# SDMAC.net
KiCad netlist of a schematic drawn in EAGLE
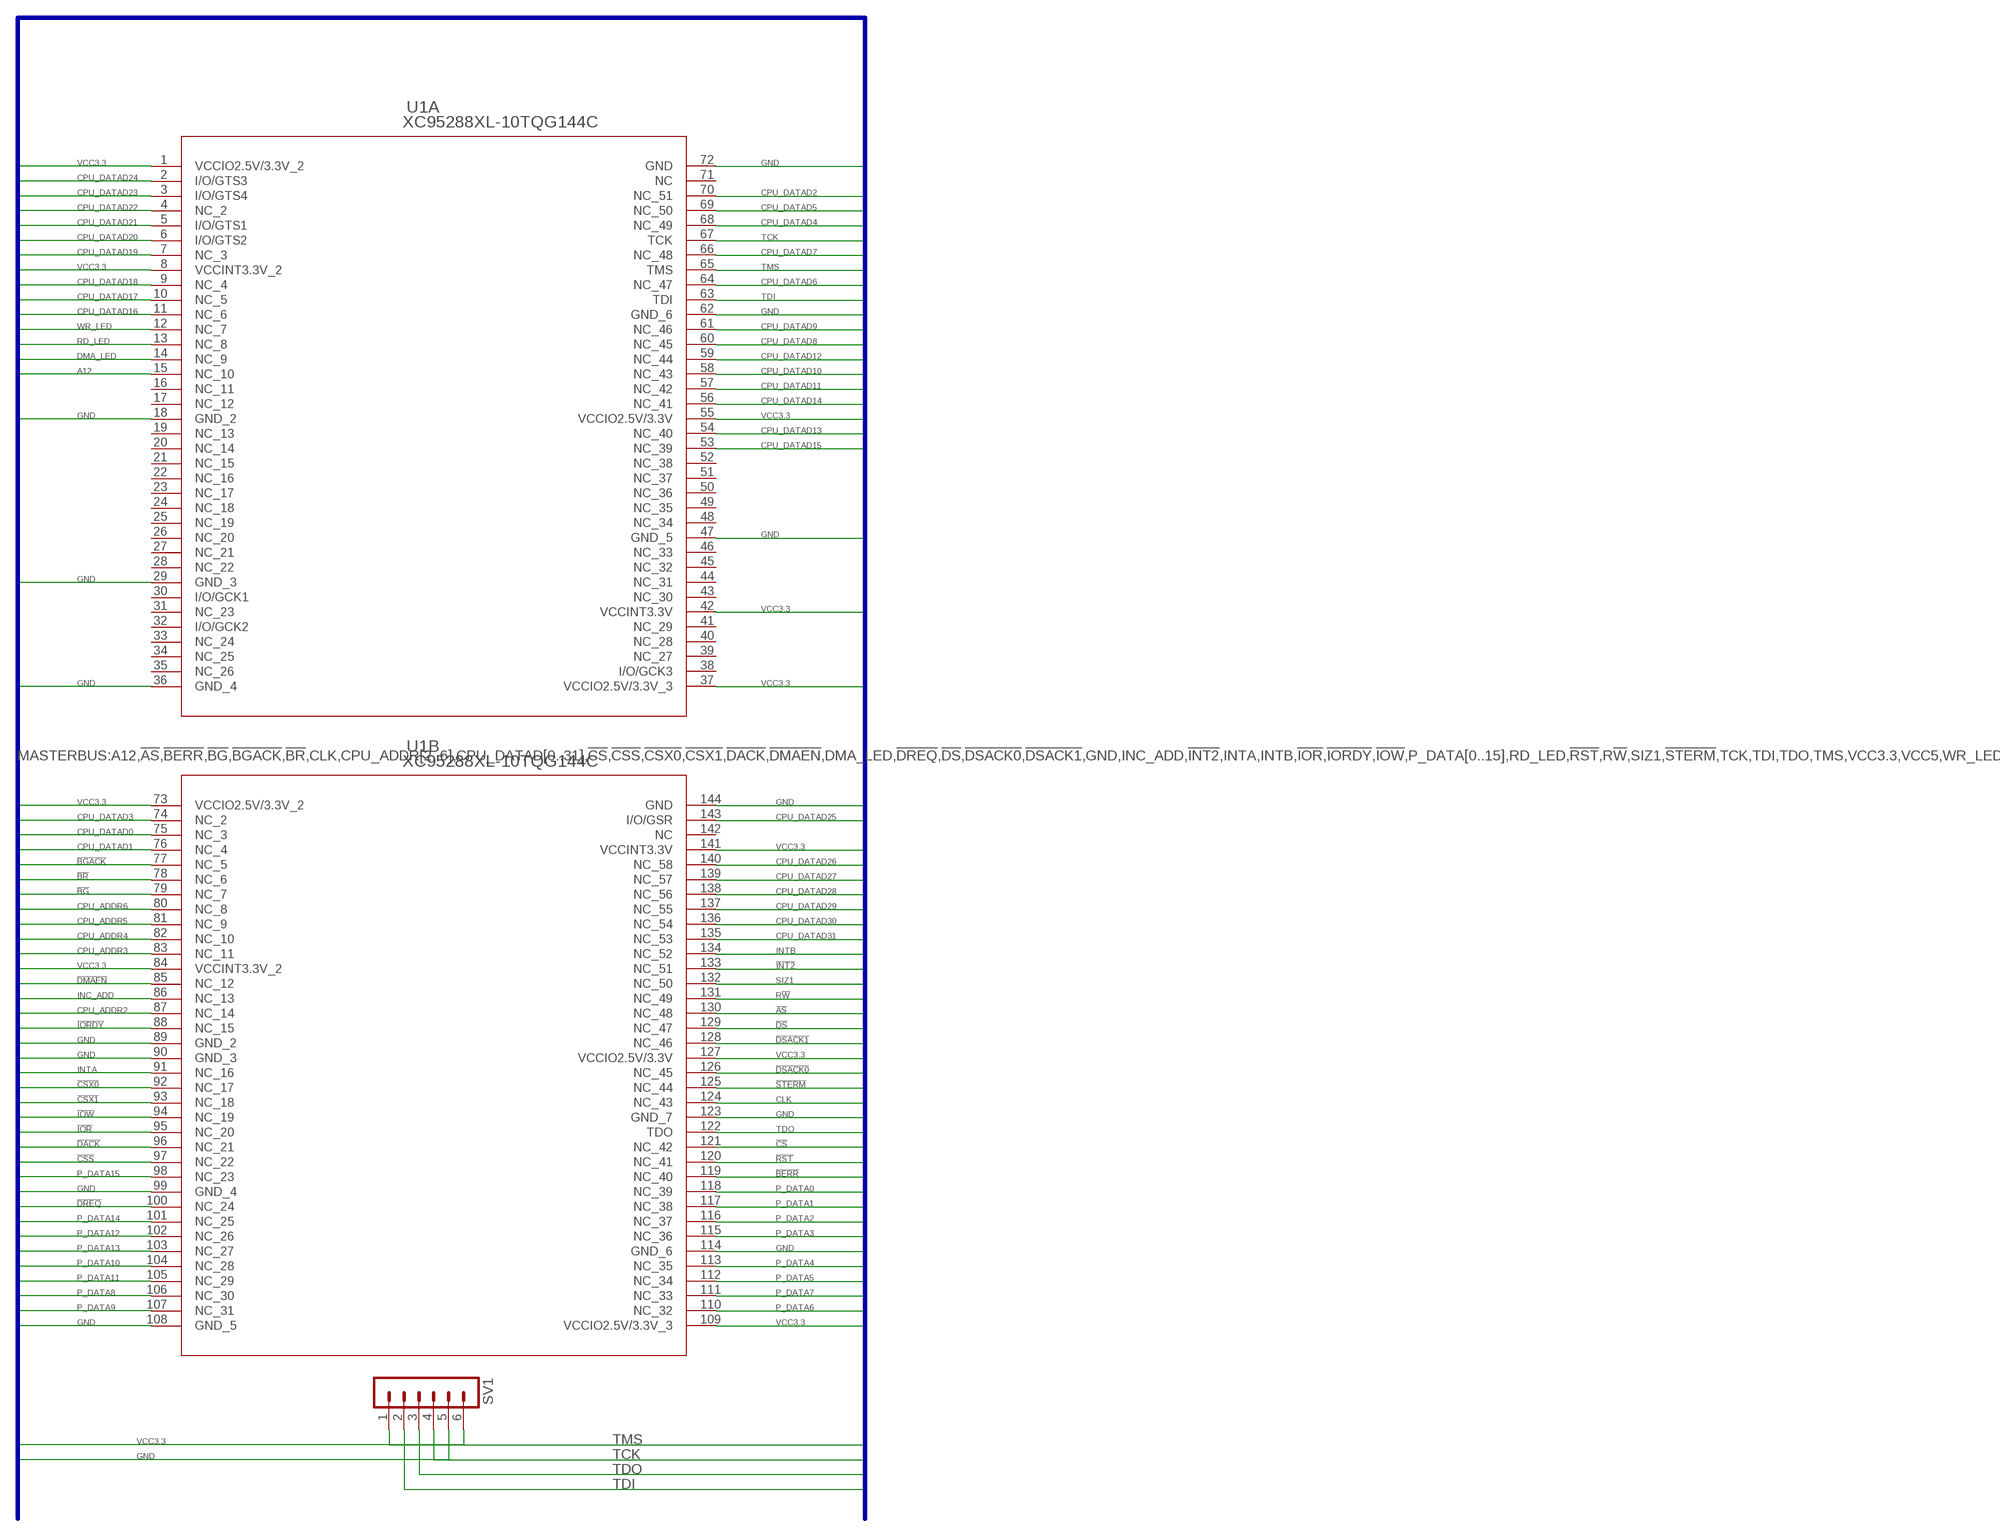
[diagram p0: schematic, sheet 1]
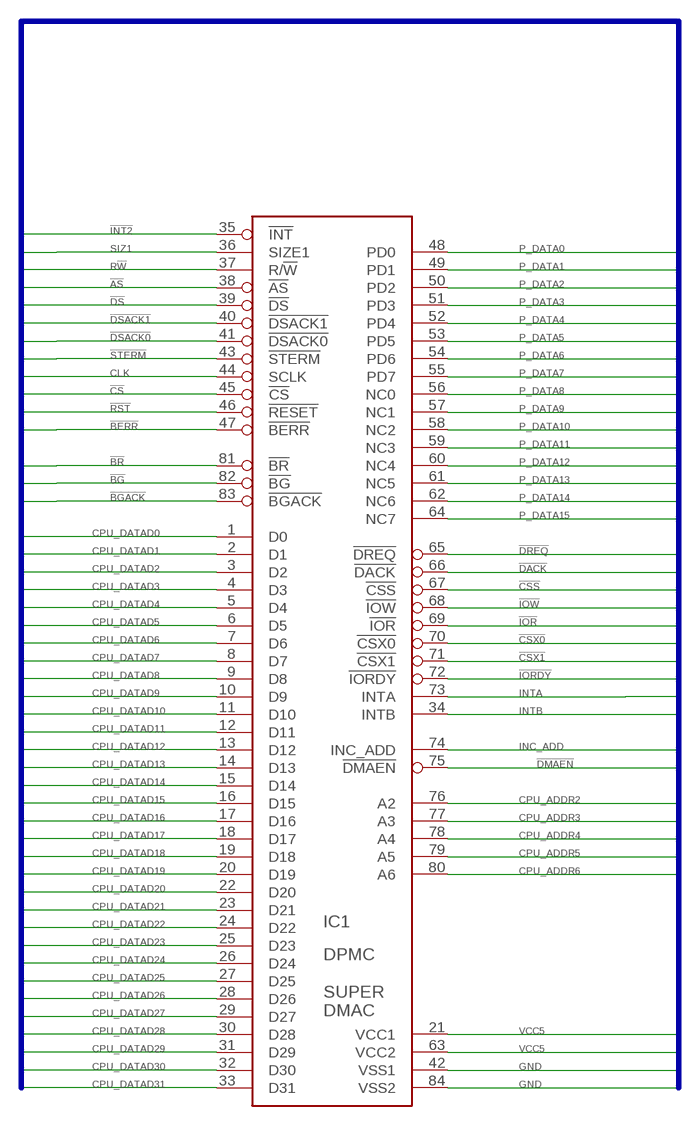
[diagram p1: schematic, sheet 2]
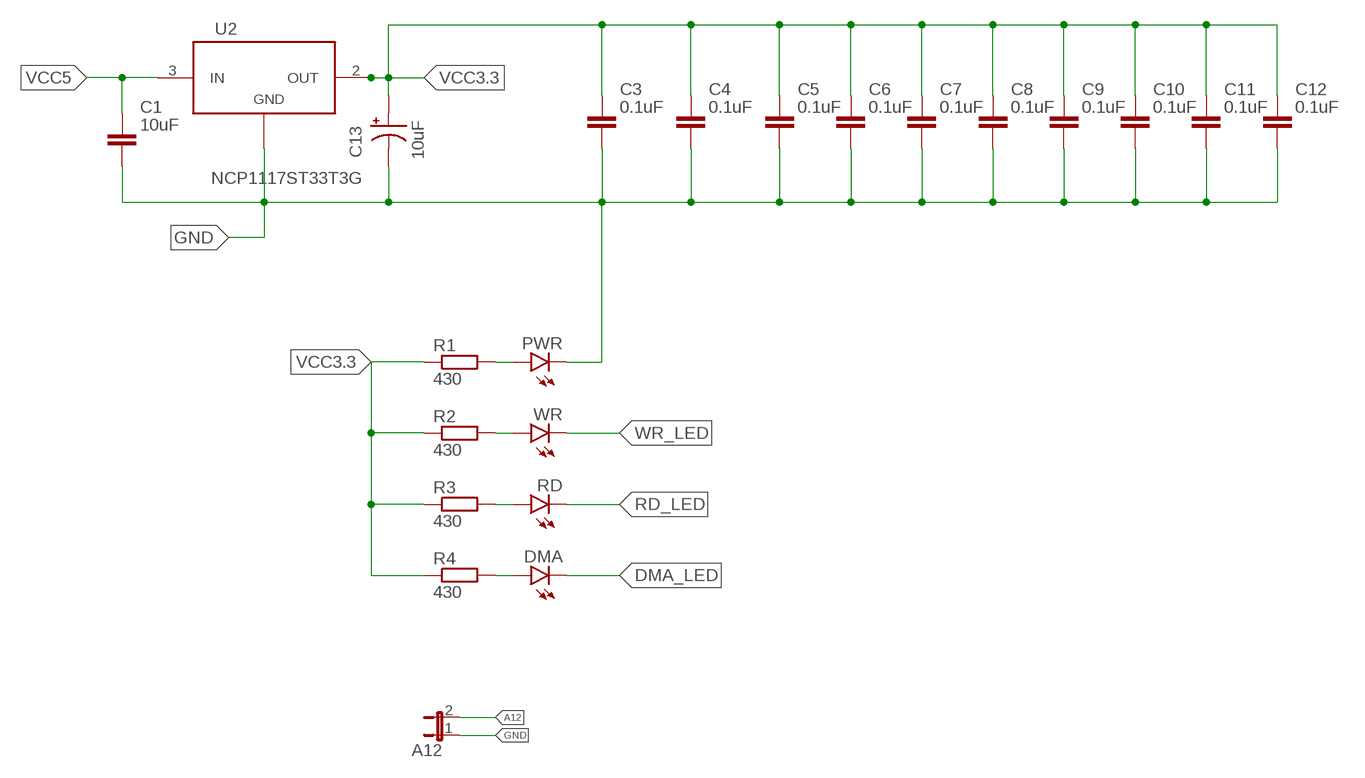
[diagram p2: schematic, sheet 3]

(export (version "E")
  (design (tool "Eeschema 10.0.6"))
  (components
    (comp (ref "IC1")
      (value "SUPER_DMAC_THT")
      (footprint "eagle-import:PLCC84_T")
      (libsource (lib "eagle-import") (part "SUPER_DMAC_THT"))
    )
    (comp (ref "A12")
      (value "JP1E")
      (footprint "eagle-import:JP1")
      (libsource (lib "eagle-import") (part "JP1E"))
    )
    (comp (ref "C1")
      (value "10uF")
      (footprint "eagle-import:CAPC2012X110")
      (libsource (lib "eagle-import") (part "CCHIP-0805(2012-METRIC)_"))
    )
    (comp (ref "C3")
      (value "0.1uF")
      (footprint "eagle-import:CAPC2012X110")
      (libsource (lib "eagle-import") (part "CCHIP-0805(2012-METRIC)_"))
    )
    (comp (ref "C4")
      (value "0.1uF")
      (footprint "eagle-import:CAPC2012X110")
      (libsource (lib "eagle-import") (part "CCHIP-0805(2012-METRIC)_"))
    )
    (comp (ref "C5")
      (value "0.1uF")
      (footprint "eagle-import:CAPC2012X110")
      (libsource (lib "eagle-import") (part "CCHIP-0805(2012-METRIC)_"))
    )
    (comp (ref "C6")
      (value "0.1uF")
      (footprint "eagle-import:CAPC2012X110")
      (libsource (lib "eagle-import") (part "CCHIP-0805(2012-METRIC)_"))
    )
    (comp (ref "C7")
      (value "0.1uF")
      (footprint "eagle-import:CAPC2012X110")
      (libsource (lib "eagle-import") (part "CCHIP-0805(2012-METRIC)_"))
    )
    (comp (ref "C8")
      (value "0.1uF")
      (footprint "eagle-import:CAPC2012X110")
      (libsource (lib "eagle-import") (part "CCHIP-0805(2012-METRIC)_"))
    )
    (comp (ref "C9")
      (value "0.1uF")
      (footprint "eagle-import:CAPC2012X110")
      (libsource (lib "eagle-import") (part "CCHIP-0805(2012-METRIC)_"))
    )
    (comp (ref "C10")
      (value "0.1uF")
      (footprint "eagle-import:CAPC2012X110")
      (libsource (lib "eagle-import") (part "CCHIP-0805(2012-METRIC)_"))
    )
    (comp (ref "C11")
      (value "0.1uF")
      (footprint "eagle-import:CAPC2012X110")
      (libsource (lib "eagle-import") (part "CCHIP-0805(2012-METRIC)_"))
    )
    (comp (ref "C12")
      (value "0.1uF")
      (footprint "eagle-import:CAPC2012X110")
      (libsource (lib "eagle-import") (part "CCHIP-0805(2012-METRIC)_"))
    )
    (comp (ref "C13")
      (value "10uF")
      (footprint "eagle-import:A")
      (fields
        (field (name "MANUFACTURER") "Kemet")
        (field (name "PART_NUMBER") "T491A106K010AT")
        (field (name "TOLERANCE") "±10%")
      )
      (libsource (lib "eagle-import") (part "T491?A106K010AT"))
    )
    (comp (ref "DMA")
      (value "LEDSML0805")
      (footprint "eagle-import:SML0805")
      (libsource (lib "eagle-import") (part "LEDSML0805"))
    )
    (comp (ref "PWR")
      (value "LEDSML0805")
      (footprint "eagle-import:SML0805")
      (libsource (lib "eagle-import") (part "LEDSML0805"))
    )
    (comp (ref "R1")
      (value "430")
      (footprint "eagle-import:R0805")
      (libsource (lib "eagle-import") (part "R-EU_R0805"))
    )
    (comp (ref "R2")
      (value "430")
      (footprint "eagle-import:R0805")
      (libsource (lib "eagle-import") (part "R-EU_R0805"))
    )
    (comp (ref "R3")
      (value "430")
      (footprint "eagle-import:R0805")
      (libsource (lib "eagle-import") (part "R-EU_R0805"))
    )
    (comp (ref "R4")
      (value "430")
      (footprint "eagle-import:R0805")
      (libsource (lib "eagle-import") (part "R-EU_R0805"))
    )
    (comp (ref "RD")
      (value "LEDSML0805")
      (footprint "eagle-import:SML0805")
      (libsource (lib "eagle-import") (part "LEDSML0805"))
    )
    (comp (ref "U2")
      (value "NCP1117ST33T3G")
      (footprint "eagle-import:SOT-223")
      (fields
        (field (name "DIGIKEY_PART_NUMBER") "NCP1117ST33T3GOSTR-ND")
        (field (name "MANUFACTURER") "ON Semiconductor")
        (field (name "CREATED_BY") "PCBLayout.com")
      )
      (libsource (lib "eagle-import") (part "NCP1117ST33T3G"))
    )
    (comp (ref "WR")
      (value "LEDSML0805")
      (footprint "eagle-import:SML0805")
      (libsource (lib "eagle-import") (part "LEDSML0805"))
    )
    (comp (ref "SV1")
      (value "MA06-1")
      (footprint "eagle-import:MA06-1")
      (fields (field (name "SPICEPREFIX") "X"))
      (libsource (lib "eagle-import") (part "MA06-1"))
    )
    (comp (ref "U1")
      (value "XC95288XL-10TQG144C")
      (footprint "eagle-import:144-TQFP_XIL")
      (fields (field (name "COPYRIGHT") "Copyright (C) 2022 Ultra Librarian. All rights reserved."))
      (libsource (lib "eagle-import") (part "XC95288XL-10TQG144C"))
    )
  )
  (nets
    (net (code "4") (name "A12") (class "Default")
      (node (ref "A12") (pin "2") (pinfunction "2_2") (pintype "passive"))
      (node (ref "U1") (pin "15") (pinfunction "NC_10_15") (pintype "passive"))
    )
    (net (code "5") (name "CLK") (class "Default")
      (node (ref "IC1") (pin "44") (pinfunction "SCLK_44") (pintype "input"))
      (node (ref "U1") (pin "124") (pinfunction "NC_43_124") (pintype "passive"))
    )
    (net (code "6") (name "CPU_ADDR2") (class "Default")
      (node (ref "IC1") (pin "76") (pinfunction "A2_76") (pintype "input"))
      (node (ref "U1") (pin "87") (pinfunction "NC_14_87") (pintype "passive"))
    )
    (net (code "7") (name "CPU_ADDR3") (class "Default")
      (node (ref "IC1") (pin "77") (pinfunction "A3_77") (pintype "input"))
      (node (ref "U1") (pin "83") (pinfunction "NC_11_83") (pintype "passive"))
    )
    (net (code "8") (name "CPU_ADDR4") (class "Default")
      (node (ref "IC1") (pin "78") (pinfunction "A4_78") (pintype "input"))
      (node (ref "U1") (pin "82") (pinfunction "NC_10_82") (pintype "passive"))
    )
    (net (code "9") (name "CPU_ADDR5") (class "Default")
      (node (ref "IC1") (pin "79") (pinfunction "A5_79") (pintype "input"))
      (node (ref "U1") (pin "81") (pinfunction "NC_9_81") (pintype "passive"))
    )
    (net (code "10") (name "CPU_ADDR6") (class "Default")
      (node (ref "IC1") (pin "80") (pinfunction "A6_80") (pintype "input"))
      (node (ref "U1") (pin "80") (pinfunction "NC_8_80") (pintype "passive"))
    )
    (net (code "11") (name "CPU_DATAD0") (class "Default")
      (node (ref "IC1") (pin "1") (pinfunction "D0_1") (pintype "bidirectional"))
      (node (ref "U1") (pin "75") (pinfunction "NC_3_75") (pintype "passive"))
    )
    (net (code "12") (name "CPU_DATAD1") (class "Default")
      (node (ref "IC1") (pin "2") (pinfunction "D1_2") (pintype "bidirectional"))
      (node (ref "U1") (pin "76") (pinfunction "NC_4_76") (pintype "passive"))
    )
    (net (code "13") (name "CPU_DATAD2") (class "Default")
      (node (ref "IC1") (pin "3") (pinfunction "D2_3") (pintype "bidirectional"))
      (node (ref "U1") (pin "70") (pinfunction "NC_51_70") (pintype "passive"))
    )
    (net (code "14") (name "CPU_DATAD3") (class "Default")
      (node (ref "IC1") (pin "4") (pinfunction "D3_4") (pintype "bidirectional"))
      (node (ref "U1") (pin "74") (pinfunction "NC_2_74") (pintype "passive"))
    )
    (net (code "15") (name "CPU_DATAD4") (class "Default")
      (node (ref "IC1") (pin "5") (pinfunction "D4_5") (pintype "bidirectional"))
      (node (ref "U1") (pin "68") (pinfunction "NC_49_68") (pintype "passive"))
    )
    (net (code "16") (name "CPU_DATAD5") (class "Default")
      (node (ref "IC1") (pin "6") (pinfunction "D5_6") (pintype "bidirectional"))
      (node (ref "U1") (pin "69") (pinfunction "NC_50_69") (pintype "passive"))
    )
    (net (code "17") (name "CPU_DATAD6") (class "Default")
      (node (ref "IC1") (pin "7") (pinfunction "D6_7") (pintype "bidirectional"))
      (node (ref "U1") (pin "64") (pinfunction "NC_47_64") (pintype "passive"))
    )
    (net (code "18") (name "CPU_DATAD7") (class "Default")
      (node (ref "IC1") (pin "8") (pinfunction "D7_8") (pintype "bidirectional"))
      (node (ref "U1") (pin "66") (pinfunction "NC_48_66") (pintype "passive"))
    )
    (net (code "19") (name "CPU_DATAD8") (class "Default")
      (node (ref "IC1") (pin "9") (pinfunction "D8_9") (pintype "bidirectional"))
      (node (ref "U1") (pin "60") (pinfunction "NC_45_60") (pintype "passive"))
    )
    (net (code "20") (name "CPU_DATAD9") (class "Default")
      (node (ref "IC1") (pin "10") (pinfunction "D9_10") (pintype "bidirectional"))
      (node (ref "U1") (pin "61") (pinfunction "NC_46_61") (pintype "passive"))
    )
    (net (code "21") (name "CPU_DATAD10") (class "Default")
      (node (ref "IC1") (pin "11") (pinfunction "D10_11") (pintype "bidirectional"))
      (node (ref "U1") (pin "58") (pinfunction "NC_43_58") (pintype "passive"))
    )
    (net (code "22") (name "CPU_DATAD11") (class "Default")
      (node (ref "IC1") (pin "12") (pinfunction "D11_12") (pintype "bidirectional"))
      (node (ref "U1") (pin "57") (pinfunction "NC_42_57") (pintype "passive"))
    )
    (net (code "23") (name "CPU_DATAD12") (class "Default")
      (node (ref "IC1") (pin "13") (pinfunction "D12_13") (pintype "bidirectional"))
      (node (ref "U1") (pin "59") (pinfunction "NC_44_59") (pintype "passive"))
    )
    (net (code "24") (name "CPU_DATAD13") (class "Default")
      (node (ref "IC1") (pin "14") (pinfunction "D13_14") (pintype "bidirectional"))
      (node (ref "U1") (pin "54") (pinfunction "NC_40_54") (pintype "passive"))
    )
    (net (code "25") (name "CPU_DATAD14") (class "Default")
      (node (ref "IC1") (pin "15") (pinfunction "D14_15") (pintype "bidirectional"))
      (node (ref "U1") (pin "56") (pinfunction "NC_41_56") (pintype "passive"))
    )
    (net (code "26") (name "CPU_DATAD15") (class "Default")
      (node (ref "IC1") (pin "16") (pinfunction "D15_16") (pintype "bidirectional"))
      (node (ref "U1") (pin "53") (pinfunction "NC_39_53") (pintype "passive"))
    )
    (net (code "27") (name "CPU_DATAD16") (class "Default")
      (node (ref "IC1") (pin "17") (pinfunction "D16_17") (pintype "bidirectional"))
      (node (ref "U1") (pin "11") (pinfunction "NC_6_11") (pintype "passive"))
    )
    (net (code "28") (name "CPU_DATAD17") (class "Default")
      (node (ref "IC1") (pin "18") (pinfunction "D17_18") (pintype "bidirectional"))
      (node (ref "U1") (pin "10") (pinfunction "NC_5_10") (pintype "passive"))
    )
    (net (code "29") (name "CPU_DATAD18") (class "Default")
      (node (ref "IC1") (pin "19") (pinfunction "D18_19") (pintype "bidirectional"))
      (node (ref "U1") (pin "9") (pinfunction "NC_4_9") (pintype "passive"))
    )
    (net (code "30") (name "CPU_DATAD19") (class "Default")
      (node (ref "IC1") (pin "20") (pinfunction "D19_20") (pintype "bidirectional"))
      (node (ref "U1") (pin "7") (pinfunction "NC_3_7") (pintype "passive"))
    )
    (net (code "31") (name "CPU_DATAD20") (class "Default")
      (node (ref "IC1") (pin "22") (pinfunction "D20_22") (pintype "bidirectional"))
      (node (ref "U1") (pin "6") (pinfunction "I/O/GTS2_6") (pintype "bidirectional"))
    )
    (net (code "32") (name "CPU_DATAD21") (class "Default")
      (node (ref "IC1") (pin "23") (pinfunction "D21_23") (pintype "bidirectional"))
      (node (ref "U1") (pin "5") (pinfunction "I/O/GTS1_5") (pintype "bidirectional"))
    )
    (net (code "33") (name "CPU_DATAD22") (class "Default")
      (node (ref "IC1") (pin "24") (pinfunction "D22_24") (pintype "bidirectional"))
      (node (ref "U1") (pin "4") (pinfunction "NC_2_4") (pintype "passive"))
    )
    (net (code "34") (name "CPU_DATAD23") (class "Default")
      (node (ref "IC1") (pin "25") (pinfunction "D23_25") (pintype "bidirectional"))
      (node (ref "U1") (pin "3") (pinfunction "I/O/GTS4_3") (pintype "bidirectional"))
    )
    (net (code "35") (name "CPU_DATAD24") (class "Default")
      (node (ref "IC1") (pin "26") (pinfunction "D24_26") (pintype "bidirectional"))
      (node (ref "U1") (pin "2") (pinfunction "I/O/GTS3_2") (pintype "bidirectional"))
    )
    (net (code "36") (name "CPU_DATAD25") (class "Default")
      (node (ref "IC1") (pin "27") (pinfunction "D25_27") (pintype "bidirectional"))
      (node (ref "U1") (pin "143") (pinfunction "I/O/GSR_143") (pintype "bidirectional"))
    )
    (net (code "37") (name "CPU_DATAD26") (class "Default")
      (node (ref "IC1") (pin "28") (pinfunction "D26_28") (pintype "bidirectional"))
      (node (ref "U1") (pin "140") (pinfunction "NC_58_140") (pintype "passive"))
    )
    (net (code "38") (name "CPU_DATAD27") (class "Default")
      (node (ref "IC1") (pin "29") (pinfunction "D27_29") (pintype "bidirectional"))
      (node (ref "U1") (pin "139") (pinfunction "NC_57_139") (pintype "passive"))
    )
    (net (code "39") (name "CPU_DATAD28") (class "Default")
      (node (ref "IC1") (pin "30") (pinfunction "D28_30") (pintype "bidirectional"))
      (node (ref "U1") (pin "138") (pinfunction "NC_56_138") (pintype "passive"))
    )
    (net (code "40") (name "CPU_DATAD29") (class "Default")
      (node (ref "IC1") (pin "31") (pinfunction "D29_31") (pintype "bidirectional"))
      (node (ref "U1") (pin "137") (pinfunction "NC_55_137") (pintype "passive"))
    )
    (net (code "41") (name "CPU_DATAD30") (class "Default")
      (node (ref "IC1") (pin "32") (pinfunction "D30_32") (pintype "bidirectional"))
      (node (ref "U1") (pin "136") (pinfunction "NC_54_136") (pintype "passive"))
    )
    (net (code "42") (name "CPU_DATAD31") (class "Default")
      (node (ref "IC1") (pin "33") (pinfunction "D31_33") (pintype "bidirectional"))
      (node (ref "U1") (pin "135") (pinfunction "NC_53_135") (pintype "passive"))
    )
    (net (code "43") (name "DMA_LED") (class "Default")
      (node (ref "DMA") (pin "C") (pinfunction "C_C") (pintype "passive"))
      (node (ref "U1") (pin "14") (pinfunction "NC_9_14") (pintype "passive"))
    )
    (net (code "44") (name "GND") (class "Default")
      (node (ref "A12") (pin "1") (pinfunction "1_1") (pintype "passive"))
      (node (ref "C1") (pin "2") (pinfunction "2_2") (pintype "passive"))
      (node (ref "C10") (pin "2") (pinfunction "2_2") (pintype "passive"))
      (node (ref "C11") (pin "2") (pinfunction "2_2") (pintype "passive"))
      (node (ref "C12") (pin "2") (pinfunction "2_2") (pintype "passive"))
      (node (ref "C13") (pin "C") (pinfunction "C_C") (pintype "passive"))
      (node (ref "C3") (pin "2") (pinfunction "2_2") (pintype "passive"))
      (node (ref "C4") (pin "2") (pinfunction "2_2") (pintype "passive"))
      (node (ref "C5") (pin "2") (pinfunction "2_2") (pintype "passive"))
      (node (ref "C6") (pin "2") (pinfunction "2_2") (pintype "passive"))
      (node (ref "C7") (pin "2") (pinfunction "2_2") (pintype "passive"))
      (node (ref "C8") (pin "2") (pinfunction "2_2") (pintype "passive"))
      (node (ref "C9") (pin "2") (pinfunction "2_2") (pintype "passive"))
      (node (ref "IC1") (pin "42") (pinfunction "VSS1_42") (pintype "power_in"))
      (node (ref "IC1") (pin "84") (pinfunction "VSS2_84") (pintype "power_in"))
      (node (ref "PWR") (pin "C") (pinfunction "C_C") (pintype "passive"))
      (node (ref "SV1") (pin "5") (pinfunction "5_5") (pintype "passive"))
      (node (ref "U1") (pin "108") (pinfunction "GND_5_108") (pintype "power_in"))
      (node (ref "U1") (pin "114") (pinfunction "GND_6_114") (pintype "power_in"))
      (node (ref "U1") (pin "123") (pinfunction "GND_7_123") (pintype "power_in"))
      (node (ref "U1") (pin "144") (pinfunction "GND_144") (pintype "power_in"))
      (node (ref "U1") (pin "18") (pinfunction "GND_2_18") (pintype "power_in"))
      (node (ref "U1") (pin "29") (pinfunction "GND_3_29") (pintype "power_in"))
      (node (ref "U1") (pin "36") (pinfunction "GND_4_36") (pintype "power_in"))
      (node (ref "U1") (pin "47") (pinfunction "GND_5_47") (pintype "power_in"))
      (node (ref "U1") (pin "62") (pinfunction "GND_6_62") (pintype "power_in"))
      (node (ref "U1") (pin "72") (pinfunction "GND_72") (pintype "power_in"))
      (node (ref "U1") (pin "89") (pinfunction "GND_2_89") (pintype "power_in"))
      (node (ref "U1") (pin "90") (pinfunction "GND_3_90") (pintype "power_in"))
      (node (ref "U1") (pin "99") (pinfunction "GND_4_99") (pintype "power_in"))
      (node (ref "U2") (pin "1") (pinfunction "ADJ/GND_1") (pintype "power_in"))
    )
    (net (code "45") (name "INC_ADD") (class "Default")
      (node (ref "IC1") (pin "74") (pinfunction "INC_ADD_74") (pintype "output"))
      (node (ref "U1") (pin "86") (pinfunction "NC_13_86") (pintype "passive"))
    )
    (net (code "46") (name "INTA") (class "Default")
      (node (ref "IC1") (pin "73") (pinfunction "INTA_73") (pintype "input"))
      (node (ref "U1") (pin "91") (pinfunction "NC_16_91") (pintype "passive"))
    )
    (net (code "47") (name "INTB") (class "Default")
      (node (ref "IC1") (pin "34") (pinfunction "INTB_34") (pintype "input"))
      (node (ref "U1") (pin "134") (pinfunction "NC_52_134") (pintype "passive"))
    )
    (net (code "48") (name "Net-(DMA-PadA)") (class "Default")
      (node (ref "DMA") (pin "A") (pinfunction "A_A") (pintype "passive"))
      (node (ref "R4") (pin "2") (pinfunction "2_2") (pintype "passive"))
    )
    (net (code "49") (name "Net-(PWR-PadA)") (class "Default")
      (node (ref "PWR") (pin "A") (pinfunction "A_A") (pintype "passive"))
      (node (ref "R1") (pin "2") (pinfunction "2_2") (pintype "passive"))
    )
    (net (code "50") (name "Net-(R2-Pad2)") (class "Default")
      (node (ref "R2") (pin "2") (pinfunction "2_2") (pintype "passive"))
      (node (ref "WR") (pin "A") (pinfunction "A_A") (pintype "passive"))
    )
    (net (code "51") (name "Net-(R3-Pad2)") (class "Default")
      (node (ref "R3") (pin "2") (pinfunction "2_2") (pintype "passive"))
      (node (ref "RD") (pin "A") (pinfunction "A_A") (pintype "passive"))
    )
    (net (code "52") (name "P_DATA0") (class "Default")
      (node (ref "IC1") (pin "48") (pinfunction "PD0_48") (pintype "bidirectional"))
      (node (ref "U1") (pin "118") (pinfunction "NC_39_118") (pintype "passive"))
    )
    (net (code "53") (name "P_DATA1") (class "Default")
      (node (ref "IC1") (pin "49") (pinfunction "PD1_49") (pintype "bidirectional"))
      (node (ref "U1") (pin "117") (pinfunction "NC_38_117") (pintype "passive"))
    )
    (net (code "54") (name "P_DATA2") (class "Default")
      (node (ref "IC1") (pin "50") (pinfunction "PD2_50") (pintype "bidirectional"))
      (node (ref "U1") (pin "116") (pinfunction "NC_37_116") (pintype "passive"))
    )
    (net (code "55") (name "P_DATA3") (class "Default")
      (node (ref "IC1") (pin "51") (pinfunction "PD3_51") (pintype "bidirectional"))
      (node (ref "U1") (pin "115") (pinfunction "NC_36_115") (pintype "passive"))
    )
    (net (code "56") (name "P_DATA4") (class "Default")
      (node (ref "IC1") (pin "52") (pinfunction "PD4_52") (pintype "bidirectional"))
      (node (ref "U1") (pin "113") (pinfunction "NC_35_113") (pintype "passive"))
    )
    (net (code "57") (name "P_DATA5") (class "Default")
      (node (ref "IC1") (pin "53") (pinfunction "PD5_53") (pintype "bidirectional"))
      (node (ref "U1") (pin "112") (pinfunction "NC_34_112") (pintype "passive"))
    )
    (net (code "58") (name "P_DATA6") (class "Default")
      (node (ref "IC1") (pin "54") (pinfunction "PD6_54") (pintype "bidirectional"))
      (node (ref "U1") (pin "110") (pinfunction "NC_32_110") (pintype "passive"))
    )
    (net (code "59") (name "P_DATA7") (class "Default")
      (node (ref "IC1") (pin "55") (pinfunction "PD7_55") (pintype "bidirectional"))
      (node (ref "U1") (pin "111") (pinfunction "NC_33_111") (pintype "passive"))
    )
    (net (code "60") (name "P_DATA8") (class "Default")
      (node (ref "IC1") (pin "56") (pinfunction "NC0_56") (pintype "bidirectional"))
      (node (ref "U1") (pin "106") (pinfunction "NC_30_106") (pintype "passive"))
    )
    (net (code "61") (name "P_DATA9") (class "Default")
      (node (ref "IC1") (pin "57") (pinfunction "NC1_57") (pintype "bidirectional"))
      (node (ref "U1") (pin "107") (pinfunction "NC_31_107") (pintype "passive"))
    )
    (net (code "62") (name "P_DATA10") (class "Default")
      (node (ref "IC1") (pin "58") (pinfunction "NC2_58") (pintype "bidirectional"))
      (node (ref "U1") (pin "104") (pinfunction "NC_28_104") (pintype "passive"))
    )
    (net (code "63") (name "P_DATA11") (class "Default")
      (node (ref "IC1") (pin "59") (pinfunction "NC3_59") (pintype "bidirectional"))
      (node (ref "U1") (pin "105") (pinfunction "NC_29_105") (pintype "passive"))
    )
    (net (code "64") (name "P_DATA12") (class "Default")
      (node (ref "IC1") (pin "60") (pinfunction "NC4_60") (pintype "bidirectional"))
      (node (ref "U1") (pin "102") (pinfunction "NC_26_102") (pintype "passive"))
    )
    (net (code "65") (name "P_DATA13") (class "Default")
      (node (ref "IC1") (pin "61") (pinfunction "NC5_61") (pintype "bidirectional"))
      (node (ref "U1") (pin "103") (pinfunction "NC_27_103") (pintype "passive"))
    )
    (net (code "66") (name "P_DATA14") (class "Default")
      (node (ref "IC1") (pin "62") (pinfunction "NC6_62") (pintype "bidirectional"))
      (node (ref "U1") (pin "101") (pinfunction "NC_25_101") (pintype "passive"))
    )
    (net (code "67") (name "P_DATA15") (class "Default")
      (node (ref "IC1") (pin "64") (pinfunction "NC7_64") (pintype "bidirectional"))
      (node (ref "U1") (pin "98") (pinfunction "NC_23_98") (pintype "passive"))
    )
    (net (code "68") (name "RD_LED") (class "Default")
      (node (ref "RD") (pin "C") (pinfunction "C_C") (pintype "passive"))
      (node (ref "U1") (pin "13") (pinfunction "NC_8_13") (pintype "passive"))
    )
    (net (code "69") (name "R~{W}") (class "Default")
      (node (ref "IC1") (pin "37") (pinfunction "R/~{W}_37") (pintype "output"))
      (node (ref "U1") (pin "131") (pinfunction "NC_49_131") (pintype "passive"))
    )
    (net (code "70") (name "SIZ1") (class "Default")
      (node (ref "IC1") (pin "36") (pinfunction "SIZE1_36") (pintype "output"))
      (node (ref "U1") (pin "132") (pinfunction "NC_50_132") (pintype "passive"))
    )
    (net (code "71") (name "TCK") (class "Default")
      (node (ref "SV1") (pin "4") (pinfunction "4_4") (pintype "passive"))
      (node (ref "U1") (pin "67") (pinfunction "TCK_67") (pintype "passive"))
    )
    (net (code "72") (name "TDI") (class "Default")
      (node (ref "SV1") (pin "2") (pinfunction "2_2") (pintype "passive"))
      (node (ref "U1") (pin "63") (pinfunction "TDI_63") (pintype "passive"))
    )
    (net (code "73") (name "TDO") (class "Default")
      (node (ref "SV1") (pin "3") (pinfunction "3_3") (pintype "passive"))
      (node (ref "U1") (pin "122") (pinfunction "TDO_122") (pintype "passive"))
    )
    (net (code "74") (name "TMS") (class "Default")
      (node (ref "SV1") (pin "1") (pinfunction "1_1") (pintype "passive"))
      (node (ref "U1") (pin "65") (pinfunction "TMS_65") (pintype "passive"))
    )
    (net (code "75") (name "VCC3.3") (class "Default")
      (node (ref "C10") (pin "1") (pinfunction "1_1") (pintype "passive"))
      (node (ref "C11") (pin "1") (pinfunction "1_1") (pintype "passive"))
      (node (ref "C12") (pin "1") (pinfunction "1_1") (pintype "passive"))
      (node (ref "C13") (pin "A") (pinfunction "A_A") (pintype "passive"))
      (node (ref "C3") (pin "1") (pinfunction "1_1") (pintype "passive"))
      (node (ref "C4") (pin "1") (pinfunction "1_1") (pintype "passive"))
      (node (ref "C5") (pin "1") (pinfunction "1_1") (pintype "passive"))
      (node (ref "C6") (pin "1") (pinfunction "1_1") (pintype "passive"))
      (node (ref "C7") (pin "1") (pinfunction "1_1") (pintype "passive"))
      (node (ref "C8") (pin "1") (pinfunction "1_1") (pintype "passive"))
      (node (ref "C9") (pin "1") (pinfunction "1_1") (pintype "passive"))
      (node (ref "R1") (pin "1") (pinfunction "1_1") (pintype "passive"))
      (node (ref "R2") (pin "1") (pinfunction "1_1") (pintype "passive"))
      (node (ref "R3") (pin "1") (pinfunction "1_1") (pintype "passive"))
      (node (ref "R4") (pin "1") (pinfunction "1_1") (pintype "passive"))
      (node (ref "SV1") (pin "6") (pinfunction "6_6") (pintype "passive"))
      (node (ref "U1") (pin "1") (pinfunction "VCCIO2.5V/3.3V_2_1") (pintype "power_in"))
      (node (ref "U1") (pin "109") (pinfunction "VCCIO2.5V/3.3V_3_109") (pintype "power_in"))
      (node (ref "U1") (pin "127") (pinfunction "VCCIO2.5V/3.3V_127") (pintype "power_in"))
      (node (ref "U1") (pin "141") (pinfunction "VCCINT3.3V_141") (pintype "power_in"))
      (node (ref "U1") (pin "37") (pinfunction "VCCIO2.5V/3.3V_3_37") (pintype "power_in"))
      (node (ref "U1") (pin "42") (pinfunction "VCCINT3.3V_42") (pintype "power_in"))
      (node (ref "U1") (pin "55") (pinfunction "VCCIO2.5V/3.3V_55") (pintype "power_in"))
      (node (ref "U1") (pin "73") (pinfunction "VCCIO2.5V/3.3V_2_73") (pintype "power_in"))
      (node (ref "U1") (pin "8") (pinfunction "VCCINT3.3V_2_8") (pintype "power_in"))
      (node (ref "U1") (pin "84") (pinfunction "VCCINT3.3V_2_84") (pintype "power_in"))
      (node (ref "U2") (pin "2") (pinfunction "OUT_2") (pintype "output"))
      (node (ref "U2") (pin "4") (pinfunction "4_4") (pintype "passive"))
    )
    (net (code "76") (name "VCC5") (class "Default")
      (node (ref "C1") (pin "1") (pinfunction "1_1") (pintype "passive"))
      (node (ref "IC1") (pin "21") (pinfunction "VCC1_21") (pintype "power_in"))
      (node (ref "IC1") (pin "63") (pinfunction "VCC2_63") (pintype "power_in"))
      (node (ref "U2") (pin "3") (pinfunction "IN_3") (pintype "input"))
    )
    (net (code "77") (name "WR_LED") (class "Default")
      (node (ref "U1") (pin "12") (pinfunction "NC_7_12") (pintype "passive"))
      (node (ref "WR") (pin "C") (pinfunction "C_C") (pintype "passive"))
    )
    (net (code "78") (name "unconnected-(U1A-I{slash}O{slash}GCK1-Pad30)") (class "Default")
      (node (ref "U1") (pin "30") (pinfunction "I/O/GCK1_30") (pintype "bidirectional"))
    )
    (net (code "79") (name "unconnected-(U1A-I{slash}O{slash}GCK2-Pad32)") (class "Default")
      (node (ref "U1") (pin "32") (pinfunction "I/O/GCK2_32") (pintype "bidirectional"))
    )
    (net (code "80") (name "unconnected-(U1A-I{slash}O{slash}GCK3-Pad38)") (class "Default")
      (node (ref "U1") (pin "38") (pinfunction "I/O/GCK3_38") (pintype "bidirectional"))
    )
    (net (code "81") (name "unconnected-(U1A-NC-Pad71)") (class "Default")
      (node (ref "U1") (pin "71") (pinfunction "NC_71") (pintype "passive"))
    )
    (net (code "82") (name "unconnected-(U1A-NC_11-Pad16)") (class "Default")
      (node (ref "U1") (pin "16") (pinfunction "NC_11_16") (pintype "passive"))
    )
    (net (code "83") (name "unconnected-(U1A-NC_12-Pad17)") (class "Default")
      (node (ref "U1") (pin "17") (pinfunction "NC_12_17") (pintype "passive"))
    )
    (net (code "84") (name "unconnected-(U1A-NC_13-Pad19)") (class "Default")
      (node (ref "U1") (pin "19") (pinfunction "NC_13_19") (pintype "passive"))
    )
    (net (code "85") (name "unconnected-(U1A-NC_14-Pad20)") (class "Default")
      (node (ref "U1") (pin "20") (pinfunction "NC_14_20") (pintype "passive"))
    )
    (net (code "86") (name "unconnected-(U1A-NC_15-Pad21)") (class "Default")
      (node (ref "U1") (pin "21") (pinfunction "NC_15_21") (pintype "passive"))
    )
    (net (code "87") (name "unconnected-(U1A-NC_16-Pad22)") (class "Default")
      (node (ref "U1") (pin "22") (pinfunction "NC_16_22") (pintype "passive"))
    )
    (net (code "88") (name "unconnected-(U1A-NC_17-Pad23)") (class "Default")
      (node (ref "U1") (pin "23") (pinfunction "NC_17_23") (pintype "passive"))
    )
    (net (code "89") (name "unconnected-(U1A-NC_18-Pad24)") (class "Default")
      (node (ref "U1") (pin "24") (pinfunction "NC_18_24") (pintype "passive"))
    )
    (net (code "90") (name "unconnected-(U1A-NC_19-Pad25)") (class "Default")
      (node (ref "U1") (pin "25") (pinfunction "NC_19_25") (pintype "passive"))
    )
    (net (code "91") (name "unconnected-(U1A-NC_20-Pad26)") (class "Default")
      (node (ref "U1") (pin "26") (pinfunction "NC_20_26") (pintype "passive"))
    )
    (net (code "92") (name "unconnected-(U1A-NC_21-Pad27)") (class "Default")
      (node (ref "U1") (pin "27") (pinfunction "NC_21_27") (pintype "passive"))
    )
    (net (code "93") (name "unconnected-(U1A-NC_22-Pad28)") (class "Default")
      (node (ref "U1") (pin "28") (pinfunction "NC_22_28") (pintype "passive"))
    )
    (net (code "94") (name "unconnected-(U1A-NC_23-Pad31)") (class "Default")
      (node (ref "U1") (pin "31") (pinfunction "NC_23_31") (pintype "passive"))
    )
    (net (code "95") (name "unconnected-(U1A-NC_24-Pad33)") (class "Default")
      (node (ref "U1") (pin "33") (pinfunction "NC_24_33") (pintype "passive"))
    )
    (net (code "96") (name "unconnected-(U1A-NC_25-Pad34)") (class "Default")
      (node (ref "U1") (pin "34") (pinfunction "NC_25_34") (pintype "passive"))
    )
    (net (code "97") (name "unconnected-(U1A-NC_26-Pad35)") (class "Default")
      (node (ref "U1") (pin "35") (pinfunction "NC_26_35") (pintype "passive"))
    )
    (net (code "98") (name "unconnected-(U1A-NC_27-Pad39)") (class "Default")
      (node (ref "U1") (pin "39") (pinfunction "NC_27_39") (pintype "passive"))
    )
    (net (code "99") (name "unconnected-(U1A-NC_28-Pad40)") (class "Default")
      (node (ref "U1") (pin "40") (pinfunction "NC_28_40") (pintype "passive"))
    )
    (net (code "100") (name "unconnected-(U1A-NC_29-Pad41)") (class "Default")
      (node (ref "U1") (pin "41") (pinfunction "NC_29_41") (pintype "passive"))
    )
    (net (code "101") (name "unconnected-(U1A-NC_30-Pad43)") (class "Default")
      (node (ref "U1") (pin "43") (pinfunction "NC_30_43") (pintype "passive"))
    )
    (net (code "102") (name "unconnected-(U1A-NC_31-Pad44)") (class "Default")
      (node (ref "U1") (pin "44") (pinfunction "NC_31_44") (pintype "passive"))
    )
    (net (code "103") (name "unconnected-(U1A-NC_32-Pad45)") (class "Default")
      (node (ref "U1") (pin "45") (pinfunction "NC_32_45") (pintype "passive"))
    )
    (net (code "104") (name "unconnected-(U1A-NC_33-Pad46)") (class "Default")
      (node (ref "U1") (pin "46") (pinfunction "NC_33_46") (pintype "passive"))
    )
    (net (code "105") (name "unconnected-(U1A-NC_34-Pad48)") (class "Default")
      (node (ref "U1") (pin "48") (pinfunction "NC_34_48") (pintype "passive"))
    )
    (net (code "106") (name "unconnected-(U1A-NC_35-Pad49)") (class "Default")
      (node (ref "U1") (pin "49") (pinfunction "NC_35_49") (pintype "passive"))
    )
    (net (code "107") (name "unconnected-(U1A-NC_36-Pad50)") (class "Default")
      (node (ref "U1") (pin "50") (pinfunction "NC_36_50") (pintype "passive"))
    )
    (net (code "108") (name "unconnected-(U1A-NC_37-Pad51)") (class "Default")
      (node (ref "U1") (pin "51") (pinfunction "NC_37_51") (pintype "passive"))
    )
    (net (code "109") (name "unconnected-(U1A-NC_38-Pad52)") (class "Default")
      (node (ref "U1") (pin "52") (pinfunction "NC_38_52") (pintype "passive"))
    )
    (net (code "110") (name "unconnected-(U1B-NC-Pad142)") (class "Default")
      (node (ref "U1") (pin "142") (pinfunction "NC_142") (pintype "passive"))
    )
    (net (code "111") (name "~{AS}") (class "Default")
      (node (ref "IC1") (pin "38") (pinfunction "~{AS}_38") (pintype "output"))
      (node (ref "U1") (pin "130") (pinfunction "NC_48_130") (pintype "passive"))
    )
    (net (code "112") (name "~{BERR}") (class "Default")
      (node (ref "IC1") (pin "47") (pinfunction "~{BERR}_47") (pintype "input"))
      (node (ref "U1") (pin "119") (pinfunction "NC_40_119") (pintype "passive"))
    )
    (net (code "113") (name "~{BGACK}") (class "Default")
      (node (ref "IC1") (pin "83") (pinfunction "~{BGACK}_83") (pintype "output"))
      (node (ref "U1") (pin "77") (pinfunction "NC_5_77") (pintype "passive"))
    )
    (net (code "114") (name "~{BG}") (class "Default")
      (node (ref "IC1") (pin "82") (pinfunction "~{BG}_82") (pintype "input"))
      (node (ref "U1") (pin "79") (pinfunction "NC_7_79") (pintype "passive"))
    )
    (net (code "115") (name "~{BR}") (class "Default")
      (node (ref "IC1") (pin "81") (pinfunction "~{BR}_81") (pintype "output"))
      (node (ref "U1") (pin "78") (pinfunction "NC_6_78") (pintype "passive"))
    )
    (net (code "116") (name "~{CSS}") (class "Default")
      (node (ref "IC1") (pin "67") (pinfunction "~{CSS}_67") (pintype "output"))
      (node (ref "U1") (pin "97") (pinfunction "NC_22_97") (pintype "passive"))
    )
    (net (code "117") (name "~{CSX0}") (class "Default")
      (node (ref "IC1") (pin "70") (pinfunction "~{CSX0}_70") (pintype "output"))
      (node (ref "U1") (pin "92") (pinfunction "NC_17_92") (pintype "passive"))
    )
    (net (code "118") (name "~{CSX1}") (class "Default")
      (node (ref "IC1") (pin "71") (pinfunction "~{CSX1}_71") (pintype "output"))
      (node (ref "U1") (pin "93") (pinfunction "NC_18_93") (pintype "passive"))
    )
    (net (code "119") (name "~{CS}") (class "Default")
      (node (ref "IC1") (pin "45") (pinfunction "~{CS}_45") (pintype "input"))
      (node (ref "U1") (pin "121") (pinfunction "NC_42_121") (pintype "passive"))
    )
    (net (code "120") (name "~{DACK}") (class "Default")
      (node (ref "IC1") (pin "66") (pinfunction "~{DACK}_66") (pintype "output"))
      (node (ref "U1") (pin "96") (pinfunction "NC_21_96") (pintype "passive"))
    )
    (net (code "121") (name "~{DMAEN}") (class "Default")
      (node (ref "IC1") (pin "75") (pinfunction "~{DMAEN}_75") (pintype "output"))
      (node (ref "U1") (pin "85") (pinfunction "NC_12_85") (pintype "passive"))
    )
    (net (code "122") (name "~{DREQ}") (class "Default")
      (node (ref "IC1") (pin "65") (pinfunction "~{DREQ}_65") (pintype "input"))
      (node (ref "U1") (pin "100") (pinfunction "NC_24_100") (pintype "passive"))
    )
    (net (code "123") (name "~{DSACK0}") (class "Default")
      (node (ref "IC1") (pin "41") (pinfunction "~{DSACK0}_41") (pintype "input"))
      (node (ref "U1") (pin "126") (pinfunction "NC_45_126") (pintype "passive"))
    )
    (net (code "124") (name "~{DSACK1}") (class "Default")
      (node (ref "IC1") (pin "40") (pinfunction "~{DSACK1}_40") (pintype "input"))
      (node (ref "U1") (pin "128") (pinfunction "NC_46_128") (pintype "passive"))
    )
    (net (code "125") (name "~{DS}") (class "Default")
      (node (ref "IC1") (pin "39") (pinfunction "~{DS}_39") (pintype "output"))
      (node (ref "U1") (pin "129") (pinfunction "NC_47_129") (pintype "passive"))
    )
    (net (code "126") (name "~{INT2}") (class "Default")
      (node (ref "IC1") (pin "35") (pinfunction "~{INT}_35") (pintype "output"))
      (node (ref "U1") (pin "133") (pinfunction "NC_51_133") (pintype "passive"))
    )
    (net (code "127") (name "~{IORDY}") (class "Default")
      (node (ref "IC1") (pin "72") (pinfunction "~{IORDY}_72") (pintype "input"))
      (node (ref "U1") (pin "88") (pinfunction "NC_15_88") (pintype "passive"))
    )
    (net (code "128") (name "~{IOR}") (class "Default")
      (node (ref "IC1") (pin "69") (pinfunction "~{IOR}_69") (pintype "output"))
      (node (ref "U1") (pin "95") (pinfunction "NC_20_95") (pintype "passive"))
    )
    (net (code "129") (name "~{IOW}") (class "Default")
      (node (ref "IC1") (pin "68") (pinfunction "~{IOW}_68") (pintype "output"))
      (node (ref "U1") (pin "94") (pinfunction "NC_19_94") (pintype "passive"))
    )
    (net (code "130") (name "~{RST}") (class "Default")
      (node (ref "IC1") (pin "46") (pinfunction "~{RESET}_46") (pintype "input"))
      (node (ref "U1") (pin "120") (pinfunction "NC_41_120") (pintype "passive"))
    )
    (net (code "131") (name "~{STERM}") (class "Default")
      (node (ref "IC1") (pin "43") (pinfunction "~{STERM}_43") (pintype "input"))
      (node (ref "U1") (pin "125") (pinfunction "NC_44_125") (pintype "passive"))
    )
  )
)
